# amp.net
KiCad netlist of a schematic drawn in EasyEDA Pro
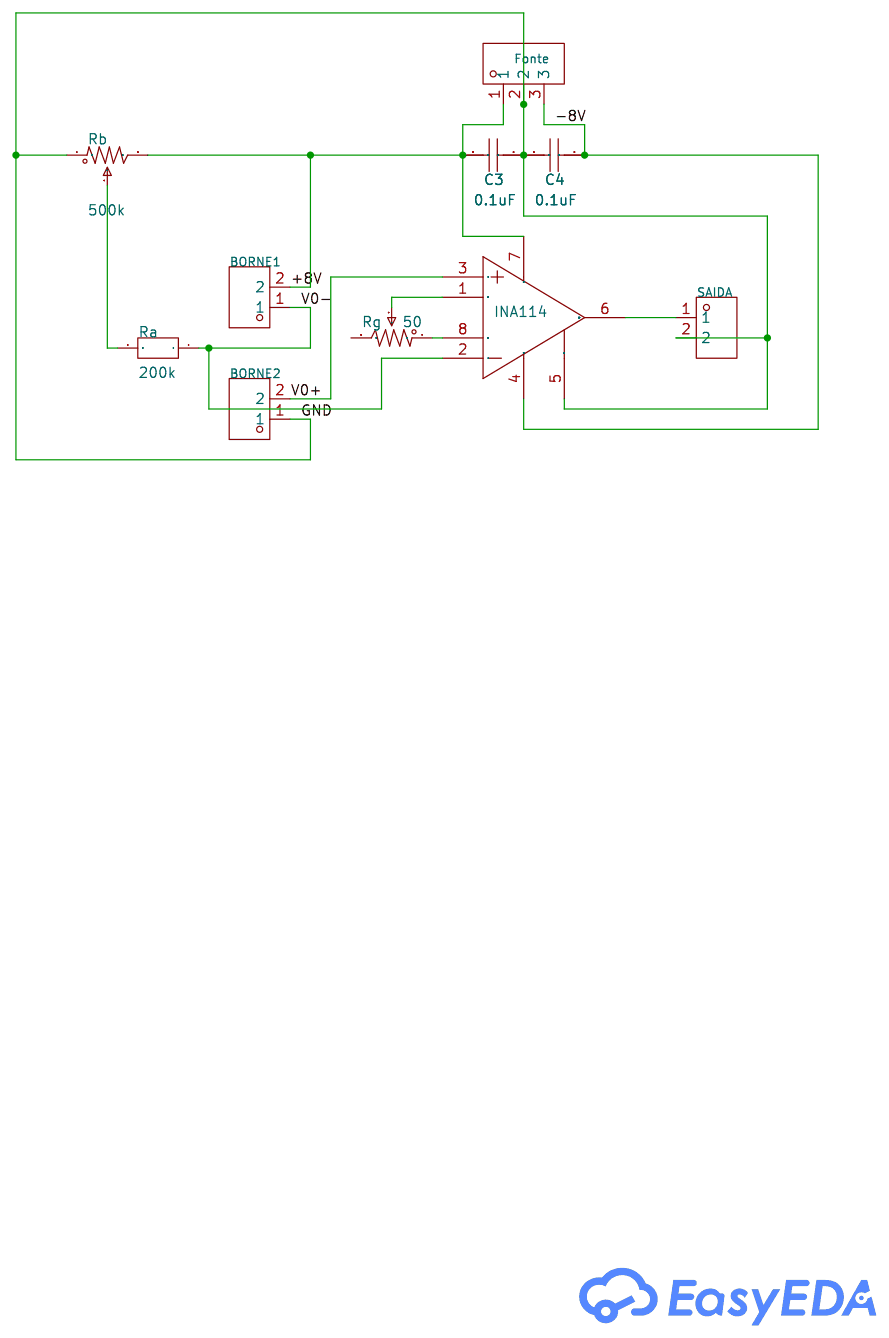
[diagram p0: schematic sheet]

(export (version "E")
  (design (tool "Eeschema 10.0.6"))
  (components
    (comp (ref "BORNE1")
      (value "KF128L-5.08-2P")
      (footprint "easyedapro:CONN-TH_P5.08_KF128L-5.08-2P")
      (fields (field (name "Manufacturer") "KEFA(科发)"))
      (libsource (lib "easyedapro") (part "KF128L-5.08-2P"))
    )
    (comp (ref "BORNE2")
      (value "KF128L-5.08-2P")
      (footprint "easyedapro:CONN-TH_P5.08_KF128L-5.08-2P")
      (fields (field (name "Manufacturer") "KEFA(科发)"))
      (libsource (lib "easyedapro") (part "KF128L-5.08-2P"))
    )
    (comp (ref "C3")
      (value "0.1uF")
      (footprint "easyedapro:CAP-TH_L8.5-W5.0-P5.00-D1.2")
      (description "Capacitance:1uF Tolerance:±10% Tolerance:±10% Voltage Rating:50V Temperature Coefficient:X7R")
      (fields (field (name "Manufacturer Part") "CT4-0805B105K500F3") (field (name "Manufacturer") "FH(风华)"))
      (libsource (lib "easyedapro") (part "CT4-0805B105K500F3"))
    )
    (comp (ref "C4")
      (value "0.1uF")
      (footprint "easyedapro:CAP-TH_L8.5-W5.0-P5.00-D1.2")
      (description "Capacitance:1uF Tolerance:±10% Tolerance:±10% Voltage Rating:50V Temperature Coefficient:X7R")
      (fields (field (name "Manufacturer Part") "CT4-0805B105K500F3") (field (name "Manufacturer") "FH(风华)"))
      (libsource (lib "easyedapro") (part "CT4-0805B105K500F3"))
    )
    (comp (ref "Fonte")
      (value "KF128-5.0-3P")
      (footprint "easyedapro:CONN-TH_3P-P5.00_KF128-5.0-3P")
      (fields (field (name "Manufacturer") "KEFA(科发)"))
      (libsource (lib "easyedapro") (part "KF128-5.0-3P"))
    )
    (comp (ref "INA114")
      (value "AD620ANZ")
      (footprint "easyedapro:DIP-8_L9.3-W6.4-P2.54-LS7.6-BL")
      (fields (field (name "Manufacturer") "ADI(亚德诺)"))
      (libsource (lib "easyedapro") (part "AD620ANZ"))
    )
    (comp (ref "Ra")
      (value "200k")
      (footprint "easyedapro:RES-TH_BD2.3-L6.5-P10.50-D0.5")
      (fields (field (name "Manufacturer Part") "MF1/4W-1KΩ±1%T52") (field (name "Manufacturer") "华星机电"))
      (libsource (lib "easyedapro") (part "MF1/4W-1KΩ±1%T52"))
    )
    (comp (ref "Rb")
      (value "500k")
      (footprint "easyedapro:RES-ADJ-TH_3P-L10.0-W10.0-P2.50-L")
      (description "Resistance: Tolerance:±10% Tolerance:±10%")
      (fields (field (name "Manufacturer Part") "3296W-1-103") (field (name "Manufacturer") "BOCHEN(博晨)"))
      (libsource (lib "easyedapro") (part "3296W-1-103"))
    )
    (comp (ref "Rg")
      (value "50")
      (footprint "easyedapro:RES-ADJ-TH_3P-L10.0-W10.0-P2.50-L")
      (description "Resistance: Tolerance:±10% Tolerance:±10%")
      (fields (field (name "Manufacturer Part") "3296W-1-103") (field (name "Manufacturer") "BOCHEN(博晨)"))
      (libsource (lib "easyedapro") (part "3296W-1-103"))
    )
    (comp (ref "SAIDA")
      (value "KF128L-5.08-2P")
      (footprint "easyedapro:CONN-TH_P5.08_KF128L-5.08-2P")
      (fields (field (name "Manufacturer") "KEFA(科发)"))
      (libsource (lib "easyedapro") (part "KF128L-5.08-2P"))
    )
  )
  (nets
    (net (code "1") (name "/+8V") (class "Default")
      (node (ref "BORNE1") (pin "2") (pinfunction "2_2") (pintype "input"))
      (node (ref "C3") (pin "1") (pinfunction "1_1") (pintype "input"))
      (node (ref "Fonte") (pin "1") (pinfunction "1_1") (pintype "input"))
      (node (ref "INA114") (pin "7") (pinfunction "+VS_7") (pintype "unspecified"))
      (node (ref "Rb") (pin "3") (pinfunction "3_3") (pintype "input"))
    )
    (net (code "2") (name "/-8V") (class "Default")
      (node (ref "C4") (pin "2") (pinfunction "2_2") (pintype "input"))
      (node (ref "Fonte") (pin "3") (pinfunction "3_3") (pintype "input"))
      (node (ref "INA114") (pin "4") (pinfunction "-VS_4") (pintype "unspecified"))
    )
    (net (code "3") (name "/GND") (class "Default")
      (node (ref "BORNE2") (pin "1") (pinfunction "1_1") (pintype "input"))
      (node (ref "C3") (pin "2") (pinfunction "2_2") (pintype "input"))
      (node (ref "C4") (pin "1") (pinfunction "1_1") (pintype "input"))
      (node (ref "Fonte") (pin "2") (pinfunction "2_2") (pintype "input"))
      (node (ref "INA114") (pin "5") (pinfunction "REF_5") (pintype "input"))
      (node (ref "Rb") (pin "1") (pinfunction "1_1") (pintype "input"))
      (node (ref "SAIDA") (pin "2") (pinfunction "2_2") (pintype "input"))
    )
    (net (code "4") (name "/V0+") (class "Default")
      (node (ref "BORNE2") (pin "2") (pinfunction "2_2") (pintype "input"))
      (node (ref "INA114") (pin "3") (pinfunction "+IN_3") (pintype "input"))
    )
    (net (code "5") (name "/V0-") (class "Default")
      (node (ref "BORNE1") (pin "1") (pinfunction "1_1") (pintype "input"))
      (node (ref "INA114") (pin "2") (pinfunction "-IN_2") (pintype "input"))
      (node (ref "Ra") (pin "1") (pinfunction "1_1") (pintype "unspecified"))
    )
    (net (code "6") (name "Net-(INA114-OUTPUT)") (class "Default")
      (node (ref "INA114") (pin "6") (pinfunction "OUTPUT_6") (pintype "output"))
      (node (ref "SAIDA") (pin "1") (pinfunction "1_1") (pintype "input"))
    )
    (net (code "7") (name "Net-(INA114-RG-Pad1)") (class "Default")
      (node (ref "INA114") (pin "1") (pinfunction "RG_1") (pintype "unspecified"))
      (node (ref "Rg") (pin "2") (pinfunction "2_2") (pintype "input"))
    )
    (net (code "8") (name "Net-(INA114-RG-Pad8)") (class "Default")
      (node (ref "INA114") (pin "8") (pinfunction "RG_8") (pintype "unspecified"))
      (node (ref "Rg") (pin "1") (pinfunction "1_1") (pintype "input"))
    )
    (net (code "9") (name "Net-(Ra-Pad2)") (class "Default")
      (node (ref "Ra") (pin "2") (pinfunction "2_2") (pintype "unspecified"))
      (node (ref "Rb") (pin "2") (pinfunction "2_2") (pintype "input"))
    )
    (net (code "10") (name "unconnected-(Rg-Pad3)") (class "Default")
      (node (ref "Rg") (pin "3") (pinfunction "3_3") (pintype "input"))
    )
  )
)
